# AnalogSignal.net
KiCad netlist of a schematic drawn in Altium Designer
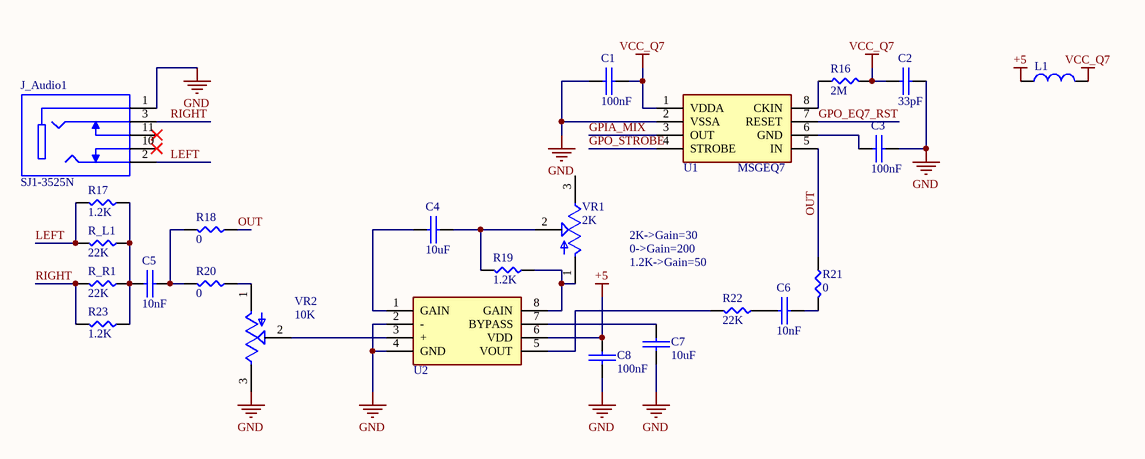
[diagram p0: AnalogSignal.SchDoc]

(export (version "E")
  (design (tool "Eeschema 10.0.6"))
  (components
    (comp (ref "C1")
      (value "100nF")
      (footprint "0603")
      (libsource (lib "altium-import") (part "root_2_Cap_"))
    )
    (comp (ref "C2") (value "33pF") (footprint "0603") (libsource (lib "altium-import") (part "root_0_Cap_")))
    (comp (ref "C3")
      (value "100nF")
      (footprint "0603")
      (libsource (lib "altium-import") (part "root_2_Cap_"))
    )
    (comp (ref "C4") (value "10uF") (footprint "0603") (libsource (lib "altium-import") (part "root_0_Cap_")))
    (comp (ref "C5") (value "10nF") (footprint "0603") (libsource (lib "altium-import") (part "root_0_Cap_")))
    (comp (ref "C6") (value "10nF") (footprint "0603") (libsource (lib "altium-import") (part "root_0_Cap_")))
    (comp (ref "C7") (value "10uF") (footprint "0603") (libsource (lib "altium-import") (part "root_1_Cap_")))
    (comp (ref "C8")
      (value "100nF")
      (footprint "0603")
      (libsource (lib "altium-import") (part "root_1_Cap_"))
    )
    (comp (ref "J_Audio1")
      (value "SJ1-3525N")
      (footprint "CUI_SJ1-3525N")
      (description "3.5 mm, Stereo, Right Angle, Through Hole, Audio Jack Connector")
      (fields (field (name "MF") "CUI Devices"))
      (libsource (lib "altium-import") (part "root_0_SJ1-3525N_"))
    )
    (comp (ref "L1") (value "~") (footprint "0603") (libsource (lib "altium-import") (part "root_0_Ind_")))
    (comp (ref "R16") (value "2M") (footprint "0603") (libsource (lib "altium-import") (part "root_0_Res_")))
    (comp (ref "R17")
      (value "1.2K")
      (footprint "0603")
      (libsource (lib "altium-import") (part "root_2_Res_"))
    )
    (comp (ref "R18") (value "0") (footprint "0603") (libsource (lib "altium-import") (part "root_2_Res_")))
    (comp (ref "R19")
      (value "1.2K")
      (footprint "0603")
      (libsource (lib "altium-import") (part "root_2_Res_"))
    )
    (comp (ref "R20") (value "0") (footprint "0603") (libsource (lib "altium-import") (part "root_2_Res_")))
    (comp (ref "R21") (value "0") (footprint "0603") (libsource (lib "altium-import") (part "root_3_Res_")))
    (comp (ref "R22") (value "22K") (footprint "0603") (libsource (lib "altium-import") (part "root_2_Res_")))
    (comp (ref "R23")
      (value "1.2K")
      (footprint "0603")
      (libsource (lib "altium-import") (part "root_2_Res_"))
    )
    (comp (ref "R_L1")
      (value "22K")
      (footprint "0603")
      (libsource (lib "altium-import") (part "root_2_Res_"))
    )
    (comp (ref "R_R1")
      (value "22K")
      (footprint "0603")
      (libsource (lib "altium-import") (part "root_2_Res_"))
    )
    (comp (ref "U1")
      (value "MSGEQ7")
      (footprint "MSGEQ7")
      (description "Seven Band Graphic Equalizer")
      (libsource (lib "altium-import") (part "root_0_MSGEQ7_"))
    )
    (comp (ref "U2")
      (value "LM386")
      (footprint "MSGEQ7")
      (description "Low Voltage Audio Power Amplifier")
      (libsource (lib "altium-import") (part "root_0_LM386_"))
    )
    (comp (ref "VR1")
      (value "2K")
      (footprint "TRIM_3362P")
      (description "PC Pins Through Hole Trimmer Potentiometer Cermet 1 Turn Top Adjustment")
      (fields (field (name "DIGI-KEY_PART_NUMBER") "3362P-103LF-ND") (field (name "MF") "Bourns"))
      (libsource (lib "FerroAudioAmp") (part "3362P"))
    )
    (comp (ref "VR2")
      (value "10K")
      (footprint "TRIM_3362P")
      (description "PC Pins Through Hole Trimmer Potentiometer Cermet 1 Turn Top Adjustment")
      (fields (field (name "DIGI-KEY_PART_NUMBER") "3362P-103LF-ND") (field (name "MF") "Bourns"))
      (libsource (lib "FerroAudioAmp") (part "3362P"))
    )
  )
  (nets
    (net (code "1") (name "+5") (class "Default")
      (node (ref "C8") (pin "2") (pinfunction "2_2") (pintype "passive"))
      (node (ref "L1") (pin "1") (pinfunction "1_1") (pintype "passive"))
      (node (ref "U2") (pin "6") (pinfunction "VDD_6") (pintype "passive"))
    )
    (net (code "2") (name "/GPIA_MIX") (class "Default")
      (node (ref "U1") (pin "3") (pinfunction "OUT_3") (pintype "passive"))
    )
    (net (code "3") (name "/GPO_EQ7_RST") (class "Default")
      (node (ref "U1") (pin "7") (pinfunction "RESET_7") (pintype "passive"))
    )
    (net (code "4") (name "/GPO_STROBE") (class "Default")
      (node (ref "U1") (pin "4") (pinfunction "STROBE_4") (pintype "passive"))
    )
    (net (code "5") (name "/LEFT") (class "Default")
      (node (ref "J_Audio1") (pin "2") (pinfunction "2_2") (pintype "passive"))
      (node (ref "R17") (pin "2") (pinfunction "2_2") (pintype "passive"))
      (node (ref "R_L1") (pin "2") (pinfunction "2_2") (pintype "passive"))
    )
    (net (code "6") (name "/OUT") (class "Default")
      (node (ref "R18") (pin "1") (pinfunction "1_1") (pintype "passive"))
      (node (ref "R21") (pin "1") (pinfunction "1_1") (pintype "passive"))
      (node (ref "U1") (pin "5") (pinfunction "IN_5") (pintype "passive"))
    )
    (net (code "7") (name "/RIGHT") (class "Default")
      (node (ref "J_Audio1") (pin "3") (pinfunction "3_3") (pintype "passive"))
      (node (ref "R23") (pin "2") (pinfunction "2_2") (pintype "passive"))
      (node (ref "R_R1") (pin "2") (pinfunction "2_2") (pintype "passive"))
    )
    (net (code "8") (name "GND") (class "Default")
      (node (ref "C1") (pin "2") (pinfunction "2_2") (pintype "passive"))
      (node (ref "C2") (pin "2") (pinfunction "2_2") (pintype "passive"))
      (node (ref "C3") (pin "1") (pinfunction "1_1") (pintype "passive"))
      (node (ref "C7") (pin "1") (pinfunction "1_1") (pintype "passive"))
      (node (ref "C8") (pin "1") (pinfunction "1_1") (pintype "passive"))
      (node (ref "J_Audio1") (pin "1") (pinfunction "1_1") (pintype "passive"))
      (node (ref "U1") (pin "2") (pinfunction "VSSA_2") (pintype "passive"))
      (node (ref "U2") (pin "2") (pinfunction "-_2") (pintype "passive"))
      (node (ref "U2") (pin "4") (pinfunction "GND_4") (pintype "passive"))
      (node (ref "VR2") (pin "3") (pinfunction "CW_3") (pintype "passive"))
    )
    (net (code "9") (name "Net-(C4-Pad1)") (class "Default")
      (node (ref "C4") (pin "1") (pinfunction "1_1") (pintype "passive"))
      (node (ref "U2") (pin "1") (pinfunction "GAIN_1") (pintype "passive"))
    )
    (net (code "10") (name "Net-(C5-Pad1)") (class "Default")
      (node (ref "C5") (pin "1") (pinfunction "1_1") (pintype "passive"))
      (node (ref "R17") (pin "1") (pinfunction "1_1") (pintype "passive"))
      (node (ref "R23") (pin "1") (pinfunction "1_1") (pintype "passive"))
      (node (ref "R_L1") (pin "1") (pinfunction "1_1") (pintype "passive"))
      (node (ref "R_R1") (pin "1") (pinfunction "1_1") (pintype "passive"))
    )
    (net (code "11") (name "Net-(C5-Pad2)") (class "Default")
      (node (ref "C5") (pin "2") (pinfunction "2_2") (pintype "passive"))
      (node (ref "R18") (pin "2") (pinfunction "2_2") (pintype "passive"))
      (node (ref "R20") (pin "2") (pinfunction "2_2") (pintype "passive"))
    )
    (net (code "12") (name "Net-(C6-Pad1)") (class "Default")
      (node (ref "C6") (pin "1") (pinfunction "1_1") (pintype "passive"))
      (node (ref "R22") (pin "1") (pinfunction "1_1") (pintype "passive"))
    )
    (net (code "13") (name "Net-(C6-Pad2)") (class "Default")
      (node (ref "C6") (pin "2") (pinfunction "2_2") (pintype "passive"))
      (node (ref "R21") (pin "2") (pinfunction "2_2") (pintype "passive"))
    )
    (net (code "14") (name "Net-(U1-CKIN)") (class "Default")
      (node (ref "R16") (pin "1") (pinfunction "1_1") (pintype "passive"))
      (node (ref "U1") (pin "8") (pinfunction "CKIN_8") (pintype "passive"))
    )
    (net (code "15") (name "Net-(U1-GND)") (class "Default")
      (node (ref "C3") (pin "2") (pinfunction "2_2") (pintype "passive"))
      (node (ref "U1") (pin "6") (pinfunction "GND_6") (pintype "passive"))
    )
    (net (code "16") (name "Net-(U2-+)") (class "Default")
      (node (ref "U2") (pin "3") (pinfunction "+_3") (pintype "passive"))
      (node (ref "VR2") (pin "2") (pinfunction "WIPER_2") (pintype "passive"))
    )
    (net (code "17") (name "Net-(U2-BYPASS)") (class "Default")
      (node (ref "C7") (pin "2") (pinfunction "2_2") (pintype "passive"))
      (node (ref "U2") (pin "7") (pinfunction "BYPASS_7") (pintype "passive"))
    )
    (net (code "18") (name "Net-(U2-VOUT)") (class "Default")
      (node (ref "R22") (pin "2") (pinfunction "2_2") (pintype "passive"))
      (node (ref "U2") (pin "5") (pinfunction "VOUT_5") (pintype "passive"))
    )
    (net (code "19") (name "Net-(VR1-CCW)") (class "Default")
      (node (ref "R19") (pin "1") (pinfunction "1_1") (pintype "passive"))
      (node (ref "U2") (pin "8") (pinfunction "GAIN_8") (pintype "passive"))
      (node (ref "VR1") (pin "1") (pinfunction "CCW_1") (pintype "passive"))
    )
    (net (code "20") (name "Net-(VR1-WIPER)") (class "Default")
      (node (ref "C4") (pin "2") (pinfunction "2_2") (pintype "passive"))
      (node (ref "R19") (pin "2") (pinfunction "2_2") (pintype "passive"))
      (node (ref "VR1") (pin "2") (pinfunction "WIPER_2") (pintype "passive"))
    )
    (net (code "21") (name "Net-(VR2-CCW)") (class "Default")
      (node (ref "R20") (pin "1") (pinfunction "1_1") (pintype "passive"))
      (node (ref "VR2") (pin "1") (pinfunction "CCW_1") (pintype "passive"))
    )
    (net (code "22") (name "VCC_Q7") (class "Default")
      (node (ref "C1") (pin "1") (pinfunction "1_1") (pintype "passive"))
      (node (ref "C2") (pin "1") (pinfunction "1_1") (pintype "passive"))
      (node (ref "L1") (pin "2") (pinfunction "2_2") (pintype "passive"))
      (node (ref "R16") (pin "2") (pinfunction "2_2") (pintype "passive"))
      (node (ref "U1") (pin "1") (pinfunction "VDDA_1") (pintype "passive"))
    )
    (net (code "23") (name "unconnected-(J_Audio1-Pad10)") (class "Default")
      (node (ref "J_Audio1") (pin "10") (pinfunction "10_10") (pintype "passive+no_connect"))
    )
    (net (code "24") (name "unconnected-(J_Audio1-Pad11)") (class "Default")
      (node (ref "J_Audio1") (pin "11") (pinfunction "11_11") (pintype "passive+no_connect"))
    )
    (net (code "25") (name "unconnected-(VR1-CW-Pad3)") (class "Default")
      (node (ref "VR1") (pin "3") (pinfunction "CW_3") (pintype "passive"))
    )
  )
)
